# Switch_board_right.net
KiCad netlist of a schematic drawn in Altium Designer
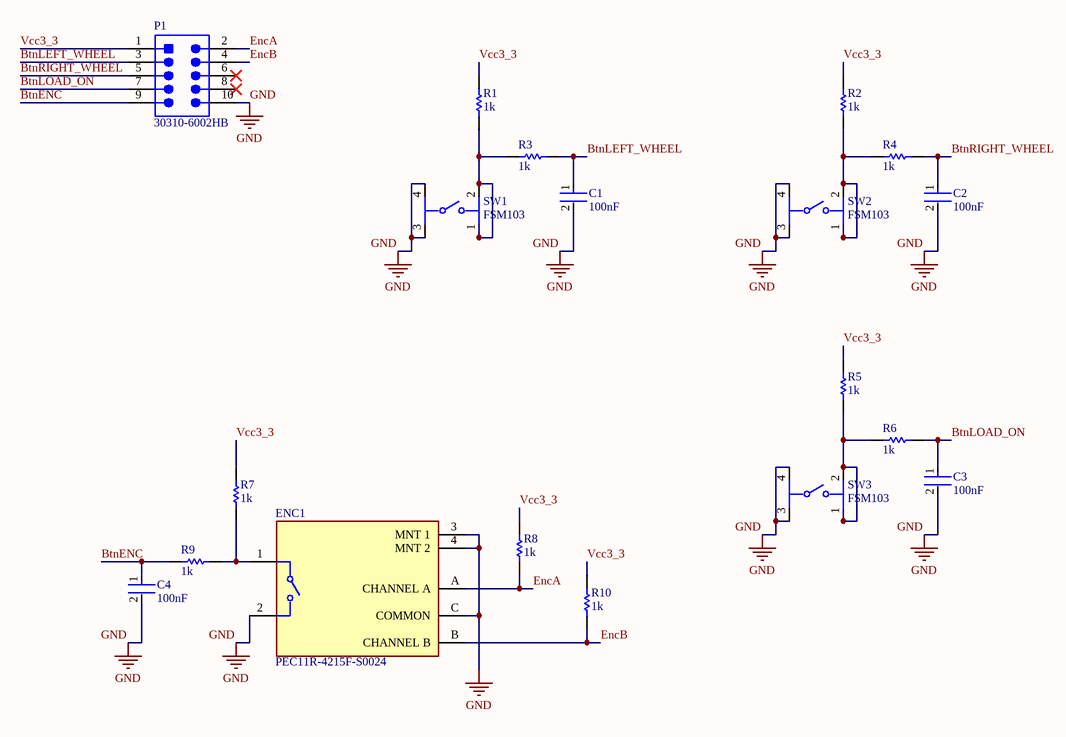
[diagram p0: Switch_board_right.SchDoc]

(export (version "E")
  (design (tool "Eeschema 10.0.6"))
  (components
    (comp (ref "C1")
      (value "100nF")
      (footprint "FP-0805-L_2_01_0_2-W_1_25-IPC_B")
      (description "General Purpose Ceramic Capacitor, 0805, 100nF, 10%, X7R, 15%, 100V")
      (fields (field (name "VOLTAGE") "100V") (field (name "TOLERANCE") "10%"))
      (libsource (lib "Altium Content Vault") (part "b4654b650e69147ec39a6b967a45e02"))
    )
    (comp (ref "C2")
      (value "100nF")
      (footprint "FP-0805-L_2_01_0_2-W_1_25-IPC_B")
      (description "General Purpose Ceramic Capacitor, 0805, 100nF, 10%, X7R, 15%, 100V")
      (fields (field (name "VOLTAGE") "100V") (field (name "TOLERANCE") "10%"))
      (libsource (lib "Altium Content Vault") (part "b4654b650e69147ec39a6b967a45e02"))
    )
    (comp (ref "C3")
      (value "100nF")
      (footprint "FP-0805-L_2_01_0_2-W_1_25-IPC_B")
      (description "General Purpose Ceramic Capacitor, 0805, 100nF, 10%, X7R, 15%, 100V")
      (fields (field (name "VOLTAGE") "100V") (field (name "TOLERANCE") "10%"))
      (libsource (lib "Altium Content Vault") (part "b4654b650e69147ec39a6b967a45e02"))
    )
    (comp (ref "C4")
      (value "100nF")
      (footprint "FP-0805-L_2_01_0_2-W_1_25-IPC_B")
      (description "General Purpose Ceramic Capacitor, 0805, 100nF, 10%, X7R, 15%, 100V")
      (fields (field (name "VOLTAGE") "100V") (field (name "TOLERANCE") "10%"))
      (libsource (lib "Altium Content Vault") (part "b4654b650e69147ec39a6b967a45e02"))
    )
    (comp (ref "ENC1")
      (value "PEC11R-4215F-S0024")
      (footprint "FP-PEC11R-4215F-S0024-MFG")
      (description "ROTARY ENCODER MECHANICAL 24PPR")
      (libsource (lib "Altium Content Vault") (part "5f1dd25a4c49fa66e7eeb899730fe11"))
    )
    (comp (ref "P1")
      (value "30310-6002HB")
      (footprint "3M-30310-6002HB-10_V")
      (fields (field (name "MANUFACTURER") "3M"))
      (libsource (lib "Altium Content Vault") (part "CN-2P-M-R10"))
    )
    (comp (ref "R1")
      (value "1k")
      (footprint "RESC2013X50X30LL20T20")
      (fields (field (name "MANUFACTURER") "Vishay Dale") (field (name "PART NUMBER") "CRCW08050000Z0EA"))
      (libsource (lib "Altium Content Vault") (part "RES"))
    )
    (comp (ref "R2")
      (value "1k")
      (footprint "RESC2013X50X30LL20T20")
      (fields (field (name "MANUFACTURER") "Vishay Dale") (field (name "PART NUMBER") "CRCW08050000Z0EA"))
      (libsource (lib "Altium Content Vault") (part "RES"))
    )
    (comp (ref "R3")
      (value "1k")
      (footprint "RESC2013X50X30LL20T20")
      (fields (field (name "MANUFACTURER") "Vishay Dale") (field (name "PART NUMBER") "CRCW08050000Z0EA"))
      (libsource (lib "Altium Content Vault") (part "RES"))
    )
    (comp (ref "R4")
      (value "1k")
      (footprint "RESC2013X50X30LL20T20")
      (fields (field (name "MANUFACTURER") "Vishay Dale") (field (name "PART NUMBER") "CRCW08050000Z0EA"))
      (libsource (lib "Altium Content Vault") (part "RES"))
    )
    (comp (ref "R5")
      (value "1k")
      (footprint "RESC2013X50X30LL20T20")
      (fields (field (name "MANUFACTURER") "Vishay Dale") (field (name "PART NUMBER") "CRCW08050000Z0EA"))
      (libsource (lib "Altium Content Vault") (part "RES"))
    )
    (comp (ref "R6")
      (value "1k")
      (footprint "RESC2013X50X30LL20T20")
      (fields (field (name "MANUFACTURER") "Vishay Dale") (field (name "PART NUMBER") "CRCW08050000Z0EA"))
      (libsource (lib "Altium Content Vault") (part "RES"))
    )
    (comp (ref "R7")
      (value "1k")
      (footprint "RESC2013X50X30LL20T20")
      (fields (field (name "MANUFACTURER") "Vishay Dale") (field (name "PART NUMBER") "CRCW08050000Z0EA"))
      (libsource (lib "Altium Content Vault") (part "RES"))
    )
    (comp (ref "R8")
      (value "1k")
      (footprint "RESC2013X50X30LL20T20")
      (fields (field (name "MANUFACTURER") "Vishay Dale") (field (name "PART NUMBER") "CRCW08050000Z0EA"))
      (libsource (lib "Altium Content Vault") (part "RES"))
    )
    (comp (ref "R9")
      (value "1k")
      (footprint "RESC2013X50X30LL20T20")
      (fields (field (name "MANUFACTURER") "Vishay Dale") (field (name "PART NUMBER") "CRCW08050000Z0EA"))
      (libsource (lib "Altium Content Vault") (part "RES"))
    )
    (comp (ref "R10")
      (value "1k")
      (footprint "RESC2013X50X30LL20T20")
      (fields (field (name "MANUFACTURER") "Vishay Dale") (field (name "PART NUMBER") "CRCW08050000Z0EA"))
      (libsource (lib "Altium Content Vault") (part "RES"))
    )
    (comp (ref "SW1")
      (value "FSM103")
      (footprint "FP-FSM103-MFG")
      (description "SWITCH TACTILE SPST-NO 0.05A 24V")
      (libsource (lib "Altium Content Vault") (part "c0df99d12937e9d2da15afdedf14b17"))
    )
    (comp (ref "SW2")
      (value "FSM103")
      (footprint "FP-FSM103-MFG")
      (description "SWITCH TACTILE SPST-NO 0.05A 24V")
      (libsource (lib "Altium Content Vault") (part "c0df99d12937e9d2da15afdedf14b17"))
    )
    (comp (ref "SW3")
      (value "FSM103")
      (footprint "FP-FSM103-MFG")
      (description "SWITCH TACTILE SPST-NO 0.05A 24V")
      (libsource (lib "Altium Content Vault") (part "c0df99d12937e9d2da15afdedf14b17"))
    )
  )
  (nets
    (net (code "1") (name "/BtnENC") (class "Default")
      (node (ref "C4") (pin "1") (pinfunction "1_1") (pintype "passive"))
      (node (ref "P1") (pin "9") (pinfunction "9_9") (pintype "passive"))
      (node (ref "R9") (pin "2") (pinfunction "2_2") (pintype "passive"))
    )
    (net (code "2") (name "/BtnLEFT_WHEEL") (class "Default")
      (node (ref "C1") (pin "1") (pinfunction "1_1") (pintype "passive"))
      (node (ref "P1") (pin "3") (pinfunction "3_3") (pintype "passive"))
      (node (ref "R3") (pin "1") (pinfunction "1_1") (pintype "passive"))
    )
    (net (code "3") (name "/BtnLOAD_ON") (class "Default")
      (node (ref "C3") (pin "1") (pinfunction "1_1") (pintype "passive"))
      (node (ref "P1") (pin "7") (pinfunction "7_7") (pintype "passive"))
      (node (ref "R6") (pin "1") (pinfunction "1_1") (pintype "passive"))
    )
    (net (code "4") (name "/BtnRIGHT_WHEEL") (class "Default")
      (node (ref "C2") (pin "1") (pinfunction "1_1") (pintype "passive"))
      (node (ref "P1") (pin "5") (pinfunction "5_5") (pintype "passive"))
      (node (ref "R4") (pin "1") (pinfunction "1_1") (pintype "passive"))
    )
    (net (code "5") (name "/EncA") (class "Default")
      (node (ref "ENC1") (pin "A") (pinfunction "CHANNEL_A_A") (pintype "passive"))
      (node (ref "P1") (pin "2") (pinfunction "2_2") (pintype "passive"))
      (node (ref "R8") (pin "1") (pinfunction "1_1") (pintype "passive"))
    )
    (net (code "6") (name "/EncB") (class "Default")
      (node (ref "ENC1") (pin "B") (pinfunction "CHANNEL_B_B") (pintype "passive"))
      (node (ref "P1") (pin "4") (pinfunction "4_4") (pintype "passive"))
      (node (ref "R10") (pin "1") (pinfunction "1_1") (pintype "passive"))
    )
    (net (code "7") (name "/Vcc3_3") (class "Default")
      (node (ref "P1") (pin "1") (pinfunction "1_1") (pintype "passive"))
      (node (ref "R1") (pin "2") (pinfunction "2_2") (pintype "passive"))
      (node (ref "R10") (pin "2") (pinfunction "2_2") (pintype "passive"))
      (node (ref "R2") (pin "2") (pinfunction "2_2") (pintype "passive"))
      (node (ref "R5") (pin "2") (pinfunction "2_2") (pintype "passive"))
      (node (ref "R7") (pin "2") (pinfunction "2_2") (pintype "passive"))
      (node (ref "R8") (pin "2") (pinfunction "2_2") (pintype "passive"))
    )
    (net (code "8") (name "GND") (class "Default")
      (node (ref "C1") (pin "2") (pinfunction "2_2") (pintype "passive"))
      (node (ref "C2") (pin "2") (pinfunction "2_2") (pintype "passive"))
      (node (ref "C3") (pin "2") (pinfunction "2_2") (pintype "passive"))
      (node (ref "C4") (pin "2") (pinfunction "2_2") (pintype "passive"))
      (node (ref "ENC1") (pin "2") (pinfunction "2_2") (pintype "passive"))
      (node (ref "ENC1") (pin "3") (pinfunction "MNT_1_3") (pintype "passive"))
      (node (ref "ENC1") (pin "4") (pinfunction "MNT_2_4") (pintype "passive"))
      (node (ref "ENC1") (pin "C") (pinfunction "COMMON_C") (pintype "passive"))
      (node (ref "P1") (pin "10") (pinfunction "10_10") (pintype "passive"))
      (node (ref "SW1") (pin "3") (pinfunction "3_3") (pintype "passive"))
      (node (ref "SW1") (pin "4") (pinfunction "4_4") (pintype "passive"))
      (node (ref "SW2") (pin "3") (pinfunction "3_3") (pintype "passive"))
      (node (ref "SW2") (pin "4") (pinfunction "4_4") (pintype "passive"))
      (node (ref "SW3") (pin "3") (pinfunction "3_3") (pintype "passive"))
      (node (ref "SW3") (pin "4") (pinfunction "4_4") (pintype "passive"))
    )
    (net (code "9") (name "Net-(ENC1-Pad1)") (class "Default")
      (node (ref "ENC1") (pin "1") (pinfunction "1_1") (pintype "passive"))
      (node (ref "R7") (pin "1") (pinfunction "1_1") (pintype "passive"))
      (node (ref "R9") (pin "1") (pinfunction "1_1") (pintype "passive"))
    )
    (net (code "10") (name "Net-(R1-Pad1)") (class "Default")
      (node (ref "R1") (pin "1") (pinfunction "1_1") (pintype "passive"))
      (node (ref "R3") (pin "2") (pinfunction "2_2") (pintype "passive"))
      (node (ref "SW1") (pin "1") (pinfunction "1_1") (pintype "passive"))
      (node (ref "SW1") (pin "2") (pinfunction "2_2") (pintype "passive"))
    )
    (net (code "11") (name "Net-(R2-Pad1)") (class "Default")
      (node (ref "R2") (pin "1") (pinfunction "1_1") (pintype "passive"))
      (node (ref "R4") (pin "2") (pinfunction "2_2") (pintype "passive"))
      (node (ref "SW2") (pin "1") (pinfunction "1_1") (pintype "passive"))
      (node (ref "SW2") (pin "2") (pinfunction "2_2") (pintype "passive"))
    )
    (net (code "12") (name "Net-(R5-Pad1)") (class "Default")
      (node (ref "R5") (pin "1") (pinfunction "1_1") (pintype "passive"))
      (node (ref "R6") (pin "2") (pinfunction "2_2") (pintype "passive"))
      (node (ref "SW3") (pin "1") (pinfunction "1_1") (pintype "passive"))
      (node (ref "SW3") (pin "2") (pinfunction "2_2") (pintype "passive"))
    )
    (net (code "13") (name "unconnected-(P1-Pad6)") (class "Default")
      (node (ref "P1") (pin "6") (pinfunction "6_6") (pintype "passive+no_connect"))
    )
    (net (code "14") (name "unconnected-(P1-Pad8)") (class "Default")
      (node (ref "P1") (pin "8") (pinfunction "8_8") (pintype "passive+no_connect"))
    )
  )
)
